# ESP8266.net
KiCad netlist of a schematic drawn in Altium Designer
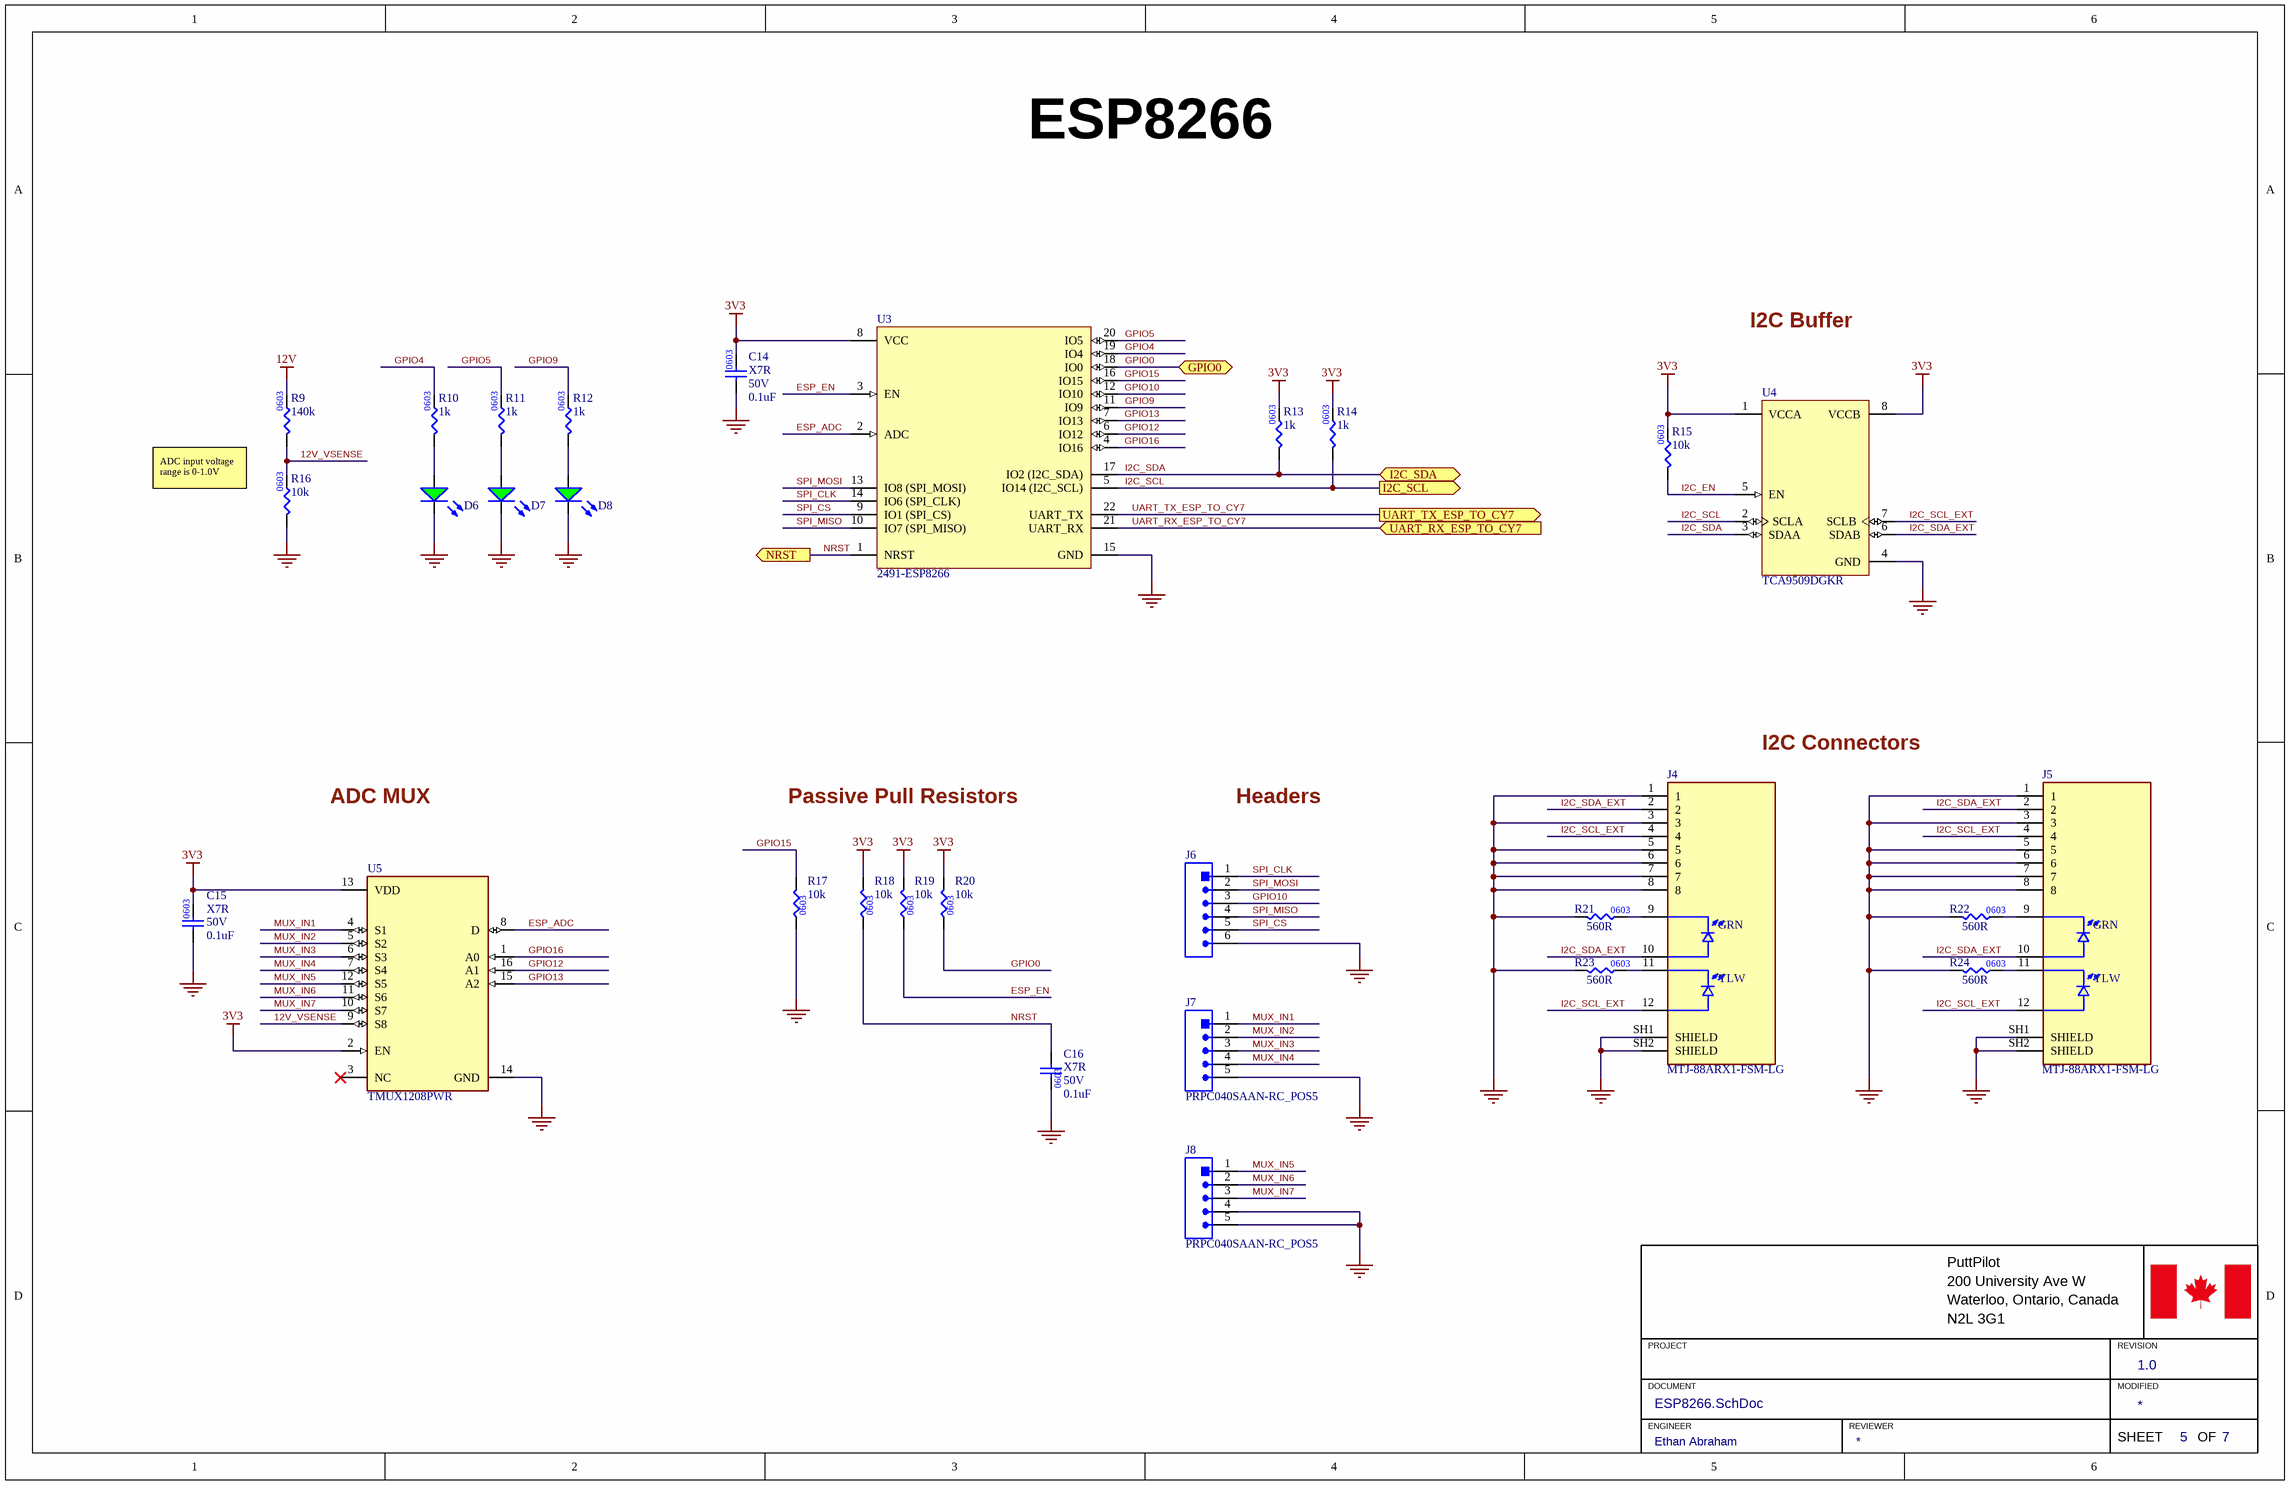
[diagram p0: ESP8266.SchDoc]

(export (version "E")
  (design (tool "Eeschema 10.0.6"))
  (components
    (comp (ref "C14")
      (value "GCJ188R71H104KA12D")
      (footprint ".CAP_0603")
      (description "CAP CER 0.1uF 50V X7R 0603")
      (fields
        (field (name "MANUFACTURER") "Murata")
        (field (name "TEMPERATURE CHARACTERISTICS CODE") "X7R")
        (field (name "RATED DC VOLTAGE (URDC)") "50V")
        (field (name "CAPACITANCE") "0.1uF")
      )
      (libsource (lib "PuttPilot") (part "GCJ188R71H104KA12D"))
    )
    (comp (ref "C15")
      (value "GCJ188R71H104KA12D")
      (footprint ".CAP_0603")
      (description "CAP CER 0.1uF 50V X7R 0603")
      (fields
        (field (name "MANUFACTURER") "Murata")
        (field (name "TEMPERATURE CHARACTERISTICS CODE") "X7R")
        (field (name "RATED DC VOLTAGE (URDC)") "50V")
        (field (name "CAPACITANCE") "0.1uF")
      )
      (libsource (lib "PuttPilot") (part "GCJ188R71H104KA12D"))
    )
    (comp (ref "C16")
      (value "GCJ188R71H104KA12D")
      (footprint ".CAP_0603")
      (description "CAP CER 0.1uF 50V X7R 0603")
      (fields
        (field (name "MANUFACTURER") "Murata")
        (field (name "TEMPERATURE CHARACTERISTICS CODE") "X7R")
        (field (name "RATED DC VOLTAGE (URDC)") "50V")
        (field (name "CAPACITANCE") "0.1uF")
      )
      (libsource (lib "PuttPilot") (part "GCJ188R71H104KA12D"))
    )
    (comp (ref "D6")
      (value "LTST-C191KGKT")
      (footprint ".LED_0603")
      (description "LED GREEN 2V 0603")
      (fields (field (name "MANUFACTURER") "Vishay Lite-On"))
      (libsource (lib "PuttPilot") (part "LTST-C191KGKT"))
    )
    (comp (ref "D7")
      (value "LTST-C191KGKT")
      (footprint ".LED_0603")
      (description "LED GREEN 2V 0603")
      (fields (field (name "MANUFACTURER") "Vishay Lite-On"))
      (libsource (lib "PuttPilot") (part "LTST-C191KGKT"))
    )
    (comp (ref "D8")
      (value "LTST-C191KGKT")
      (footprint ".LED_0603")
      (description "LED GREEN 2V 0603")
      (fields (field (name "MANUFACTURER") "Vishay Lite-On"))
      (libsource (lib "PuttPilot") (part "LTST-C191KGKT"))
    )
    (comp (ref "J4")
      (value "MTJ-88ARX1-FSM-LG")
      (footprint "MTJ-88ARX1-FSM-LG")
      (description "RJ45 JACK R/A SHIELDED")
      (fields (field (name "MANUFACTURER") "Adam Equipment"))
      (libsource (lib "PuttPilot") (part "MTJ-88ARX1-FSM-LG"))
    )
    (comp (ref "J5")
      (value "MTJ-88ARX1-FSM-LG")
      (footprint "MTJ-88ARX1-FSM-LG")
      (description "RJ45 JACK R/A SHIELDED")
      (fields (field (name "MANUFACTURER") "Adam Equipment"))
      (libsource (lib "PuttPilot") (part "MTJ-88ARX1-FSM-LG"))
    )
    (comp (ref "J6")
      (value "PRPC040SAAN-RC_POS6")
      (footprint "HEADER_6POS_2.54MM")
      (description "CONN HEADER VERT 6POS 2.54MM")
      (libsource (lib "PuttPilot") (part "PRPC040SAAN-RC_POS6"))
    )
    (comp (ref "J7")
      (value "PRPC040SAAN-RC_POS5")
      (footprint "HEADER_5POS_2.54MM")
      (description "CONN HEADER VERT 5POS 2.54MM")
      (libsource (lib "PuttPilot") (part "PRPC040SAAN-RC_POS5"))
    )
    (comp (ref "J8")
      (value "PRPC040SAAN-RC_POS5")
      (footprint "HEADER_5POS_2.54MM")
      (description "CONN HEADER VERT 5POS 2.54MM")
      (libsource (lib "PuttPilot") (part "PRPC040SAAN-RC_POS5"))
    )
    (comp (ref "R9")
      (value "RC0603FR-07140KL")
      (footprint ".RES_0603")
      (description "RES 140K OHM 0603")
      (fields
        (field (name "MANUFACTURER") "Yageo")
        (field (name "TOLERANCE") "1%")
        (field (name "RESISTANCE") "140k")
      )
      (libsource (lib "PuttPilot") (part "RC0603FR-07140KL"))
    )
    (comp (ref "R10")
      (value "RC0603FR-071KL")
      (footprint ".RES_0603")
      (description "RES 1K OHM 0603")
      (fields
        (field (name "MANUFACTURER") "Yageo")
        (field (name "TOLERANCE") "1%")
        (field (name "RESISTANCE") "1k")
      )
      (libsource (lib "PuttPilot") (part "RC0603FR-071KL"))
    )
    (comp (ref "R11")
      (value "RC0603FR-071KL")
      (footprint ".RES_0603")
      (description "RES 1K OHM 0603")
      (fields
        (field (name "MANUFACTURER") "Yageo")
        (field (name "TOLERANCE") "1%")
        (field (name "RESISTANCE") "1k")
      )
      (libsource (lib "PuttPilot") (part "RC0603FR-071KL"))
    )
    (comp (ref "R12")
      (value "RC0603FR-071KL")
      (footprint ".RES_0603")
      (description "RES 1K OHM 0603")
      (fields
        (field (name "MANUFACTURER") "Yageo")
        (field (name "TOLERANCE") "1%")
        (field (name "RESISTANCE") "1k")
      )
      (libsource (lib "PuttPilot") (part "RC0603FR-071KL"))
    )
    (comp (ref "R13")
      (value "RC0603FR-071KL")
      (footprint ".RES_0603")
      (description "RES 1K OHM 0603")
      (fields
        (field (name "MANUFACTURER") "Yageo")
        (field (name "TOLERANCE") "1%")
        (field (name "RESISTANCE") "1k")
      )
      (libsource (lib "PuttPilot") (part "RC0603FR-071KL"))
    )
    (comp (ref "R14")
      (value "RC0603FR-071KL")
      (footprint ".RES_0603")
      (description "RES 1K OHM 0603")
      (fields
        (field (name "MANUFACTURER") "Yageo")
        (field (name "TOLERANCE") "1%")
        (field (name "RESISTANCE") "1k")
      )
      (libsource (lib "PuttPilot") (part "RC0603FR-071KL"))
    )
    (comp (ref "R15")
      (value "RC0603FR-0710KL")
      (footprint ".RES_0603")
      (description "RES 10K OHM 0603")
      (fields
        (field (name "MANUFACTURER") "Yageo")
        (field (name "TOLERANCE") "1%")
        (field (name "RESISTANCE") "10k")
      )
      (libsource (lib "PuttPilot") (part "RC0603FR-0710KL"))
    )
    (comp (ref "R16")
      (value "RC0603FR-0710KL")
      (footprint ".RES_0603")
      (description "RES 10K OHM 0603")
      (fields
        (field (name "MANUFACTURER") "Yageo")
        (field (name "TOLERANCE") "1%")
        (field (name "RESISTANCE") "10k")
      )
      (libsource (lib "PuttPilot") (part "RC0603FR-0710KL"))
    )
    (comp (ref "R17")
      (value "RC0603FR-0710KL")
      (footprint ".RES_0603")
      (description "RES 10K OHM 0603")
      (fields
        (field (name "MANUFACTURER") "Yageo")
        (field (name "TOLERANCE") "1%")
        (field (name "RESISTANCE") "10k")
      )
      (libsource (lib "PuttPilot") (part "RC0603FR-0710KL"))
    )
    (comp (ref "R18")
      (value "RC0603FR-0710KL")
      (footprint ".RES_0603")
      (description "RES 10K OHM 0603")
      (fields
        (field (name "MANUFACTURER") "Yageo")
        (field (name "TOLERANCE") "1%")
        (field (name "RESISTANCE") "10k")
      )
      (libsource (lib "PuttPilot") (part "RC0603FR-0710KL"))
    )
    (comp (ref "R19")
      (value "RC0603FR-0710KL")
      (footprint ".RES_0603")
      (description "RES 10K OHM 0603")
      (fields
        (field (name "MANUFACTURER") "Yageo")
        (field (name "TOLERANCE") "1%")
        (field (name "RESISTANCE") "10k")
      )
      (libsource (lib "PuttPilot") (part "RC0603FR-0710KL"))
    )
    (comp (ref "R20")
      (value "RC0603FR-0710KL")
      (footprint ".RES_0603")
      (description "RES 10K OHM 0603")
      (fields
        (field (name "MANUFACTURER") "Yageo")
        (field (name "TOLERANCE") "1%")
        (field (name "RESISTANCE") "10k")
      )
      (libsource (lib "PuttPilot") (part "RC0603FR-0710KL"))
    )
    (comp (ref "R21")
      (value "RC0603FR-07560RL")
      (footprint ".RES_0603")
      (description "RES 560 OHM 0603")
      (fields
        (field (name "MANUFACTURER") "Yageo")
        (field (name "TOLERANCE") "1%")
        (field (name "RESISTANCE") "560R")
      )
      (libsource (lib "PuttPilot") (part "RC0603FR-07560RL"))
    )
    (comp (ref "R22")
      (value "RC0603FR-07560RL")
      (footprint ".RES_0603")
      (description "RES 560 OHM 0603")
      (fields
        (field (name "MANUFACTURER") "Yageo")
        (field (name "TOLERANCE") "1%")
        (field (name "RESISTANCE") "560R")
      )
      (libsource (lib "PuttPilot") (part "RC0603FR-07560RL"))
    )
    (comp (ref "R23")
      (value "RC0603FR-07560RL")
      (footprint ".RES_0603")
      (description "RES 560 OHM 0603")
      (fields
        (field (name "MANUFACTURER") "Yageo")
        (field (name "TOLERANCE") "1%")
        (field (name "RESISTANCE") "560R")
      )
      (libsource (lib "PuttPilot") (part "RC0603FR-07560RL"))
    )
    (comp (ref "R24")
      (value "RC0603FR-07560RL")
      (footprint ".RES_0603")
      (description "RES 560 OHM 0603")
      (fields
        (field (name "MANUFACTURER") "Yageo")
        (field (name "TOLERANCE") "1%")
        (field (name "RESISTANCE") "560R")
      )
      (libsource (lib "PuttPilot") (part "RC0603FR-07560RL"))
    )
    (comp (ref "U3")
      (value "2491-ESP8266")
      (footprint "2491-ESP8266")
      (description "ESP8266 + Trace Antenna, 4MB Flash")
      (libsource (lib "PuttPilot") (part "2491-ESP8266"))
    )
    (comp (ref "U4")
      (value "TCA9509DGKR")
      (footprint "TCA9509DGKR")
      (description "I2C BUFFER IC")
      (fields (field (name "MANUFACTURER") "Texas Instruments"))
      (libsource (lib "PuttPilot") (part "TCA9509DGKR"))
    )
    (comp (ref "U5")
      (value "TMUX1208PWR")
      (footprint "TMUX1208")
      (description "Single-Ended Multiplexer, 1 Func, 8 Channel, CMOS, PDSO16")
      (fields (field (name "MANUFACTURER") "Texas Instruments"))
      (libsource (lib "PuttPilot") (part "TMUX1208PWR"))
    )
  )
  (nets
    (net (code "1") (name "/12V_VSENSE") (class "Default")
      (node (ref "R16") (pin "2") (pinfunction "2_2") (pintype "passive"))
      (node (ref "R9") (pin "1") (pinfunction "1_1") (pintype "passive"))
      (node (ref "U5") (pin "9") (pinfunction "S8_9") (pintype "bidirectional"))
    )
    (net (code "2") (name "/ESP_ADC") (class "Default")
      (node (ref "U3") (pin "2") (pinfunction "ADC_2") (pintype "input"))
      (node (ref "U5") (pin "8") (pinfunction "D_8") (pintype "bidirectional"))
    )
    (net (code "3") (name "/ESP_EN") (class "Default")
      (node (ref "R19") (pin "1") (pinfunction "1_1") (pintype "passive"))
      (node (ref "U3") (pin "3") (pinfunction "EN_3") (pintype "input"))
    )
    (net (code "4") (name "/GPIO0") (class "Default")
      (node (ref "R20") (pin "1") (pinfunction "1_1") (pintype "passive"))
      (node (ref "U3") (pin "18") (pinfunction "IO0_18") (pintype "bidirectional"))
    )
    (net (code "5") (name "/GPIO4") (class "Default")
      (node (ref "R10") (pin "2") (pinfunction "2_2") (pintype "passive"))
      (node (ref "U3") (pin "19") (pinfunction "IO4_19") (pintype "bidirectional"))
    )
    (net (code "6") (name "/GPIO5") (class "Default")
      (node (ref "R11") (pin "2") (pinfunction "2_2") (pintype "passive"))
      (node (ref "U3") (pin "20") (pinfunction "IO5_20") (pintype "bidirectional"))
    )
    (net (code "7") (name "/GPIO9") (class "Default")
      (node (ref "R12") (pin "2") (pinfunction "2_2") (pintype "passive"))
      (node (ref "U3") (pin "11") (pinfunction "IO9_11") (pintype "bidirectional"))
    )
    (net (code "8") (name "/GPIO10") (class "Default")
      (node (ref "J6") (pin "3") (pinfunction "3_3") (pintype "passive"))
      (node (ref "U3") (pin "12") (pinfunction "IO10_12") (pintype "bidirectional"))
    )
    (net (code "9") (name "/GPIO12") (class "Default")
      (node (ref "U3") (pin "6") (pinfunction "IO12_6") (pintype "bidirectional"))
      (node (ref "U5") (pin "16") (pinfunction "A1_16") (pintype "input"))
    )
    (net (code "10") (name "/GPIO13") (class "Default")
      (node (ref "U3") (pin "7") (pinfunction "IO13_7") (pintype "bidirectional"))
      (node (ref "U5") (pin "15") (pinfunction "A2_15") (pintype "input"))
    )
    (net (code "11") (name "/GPIO15") (class "Default")
      (node (ref "R17") (pin "2") (pinfunction "2_2") (pintype "passive"))
      (node (ref "U3") (pin "16") (pinfunction "IO15_16") (pintype "bidirectional"))
    )
    (net (code "12") (name "/GPIO16") (class "Default")
      (node (ref "U3") (pin "4") (pinfunction "IO16_4") (pintype "bidirectional"))
      (node (ref "U5") (pin "1") (pinfunction "A0_1") (pintype "input"))
    )
    (net (code "13") (name "/I2C_EN") (class "Default")
      (node (ref "R15") (pin "1") (pinfunction "1_1") (pintype "passive"))
      (node (ref "U4") (pin "5") (pinfunction "EN_5") (pintype "input"))
    )
    (net (code "14") (name "/I2C_SCL") (class "Default")
      (node (ref "R14") (pin "1") (pinfunction "1_1") (pintype "passive"))
      (node (ref "U3") (pin "5") (pinfunction "IO14_(I2C_SCL)_5") (pintype "passive"))
      (node (ref "U4") (pin "2") (pinfunction "SCLA_2") (pintype "bidirectional"))
    )
    (net (code "15") (name "/I2C_SCL_EXT") (class "Default")
      (node (ref "J4") (pin "12") (pinfunction "12_12") (pintype "passive"))
      (node (ref "J4") (pin "4") (pinfunction "4_4") (pintype "passive"))
      (node (ref "J5") (pin "12") (pinfunction "12_12") (pintype "passive"))
      (node (ref "J5") (pin "4") (pinfunction "4_4") (pintype "passive"))
      (node (ref "U4") (pin "7") (pinfunction "SCLB_7") (pintype "bidirectional"))
    )
    (net (code "16") (name "/I2C_SDA") (class "Default")
      (node (ref "R13") (pin "1") (pinfunction "1_1") (pintype "passive"))
      (node (ref "U3") (pin "17") (pinfunction "IO2_(I2C_SDA)_17") (pintype "passive"))
      (node (ref "U4") (pin "3") (pinfunction "SDAA_3") (pintype "bidirectional"))
    )
    (net (code "17") (name "/I2C_SDA_EXT") (class "Default")
      (node (ref "J4") (pin "10") (pinfunction "10_10") (pintype "passive"))
      (node (ref "J4") (pin "2") (pinfunction "2_2") (pintype "passive"))
      (node (ref "J5") (pin "10") (pinfunction "10_10") (pintype "passive"))
      (node (ref "J5") (pin "2") (pinfunction "2_2") (pintype "passive"))
      (node (ref "U4") (pin "6") (pinfunction "SDAB_6") (pintype "bidirectional"))
    )
    (net (code "18") (name "/MUX_IN1") (class "Default")
      (node (ref "J7") (pin "1") (pinfunction "1_1") (pintype "passive"))
      (node (ref "U5") (pin "4") (pinfunction "S1_4") (pintype "bidirectional"))
    )
    (net (code "19") (name "/MUX_IN2") (class "Default")
      (node (ref "J7") (pin "2") (pinfunction "2_2") (pintype "passive"))
      (node (ref "U5") (pin "5") (pinfunction "S2_5") (pintype "bidirectional"))
    )
    (net (code "20") (name "/MUX_IN3") (class "Default")
      (node (ref "J7") (pin "3") (pinfunction "3_3") (pintype "passive"))
      (node (ref "U5") (pin "6") (pinfunction "S3_6") (pintype "bidirectional"))
    )
    (net (code "21") (name "/MUX_IN4") (class "Default")
      (node (ref "J7") (pin "4") (pinfunction "4_4") (pintype "passive"))
      (node (ref "U5") (pin "7") (pinfunction "S4_7") (pintype "bidirectional"))
    )
    (net (code "22") (name "/MUX_IN5") (class "Default")
      (node (ref "J8") (pin "1") (pinfunction "1_1") (pintype "passive"))
      (node (ref "U5") (pin "12") (pinfunction "S5_12") (pintype "bidirectional"))
    )
    (net (code "23") (name "/MUX_IN6") (class "Default")
      (node (ref "J8") (pin "2") (pinfunction "2_2") (pintype "passive"))
      (node (ref "U5") (pin "11") (pinfunction "S6_11") (pintype "bidirectional"))
    )
    (net (code "24") (name "/MUX_IN7") (class "Default")
      (node (ref "J8") (pin "3") (pinfunction "3_3") (pintype "passive"))
      (node (ref "U5") (pin "10") (pinfunction "S7_10") (pintype "bidirectional"))
    )
    (net (code "25") (name "/NRST") (class "Default")
      (node (ref "C16") (pin "2") (pinfunction "2_2") (pintype "passive"))
      (node (ref "R18") (pin "1") (pinfunction "1_1") (pintype "passive"))
      (node (ref "U3") (pin "1") (pinfunction "NRST_1") (pintype "passive"))
    )
    (net (code "26") (name "/SPI_CLK") (class "Default")
      (node (ref "J6") (pin "1") (pinfunction "1_1") (pintype "passive"))
      (node (ref "U3") (pin "14") (pinfunction "IO6_(SPI_CLK)_14") (pintype "passive"))
    )
    (net (code "27") (name "/SPI_CS") (class "Default")
      (node (ref "J6") (pin "5") (pinfunction "5_5") (pintype "passive"))
      (node (ref "U3") (pin "9") (pinfunction "IO1_(SPI_CS)_9") (pintype "passive"))
    )
    (net (code "28") (name "/SPI_MISO") (class "Default")
      (node (ref "J6") (pin "4") (pinfunction "4_4") (pintype "passive"))
      (node (ref "U3") (pin "10") (pinfunction "IO7_(SPI_MISO)_10") (pintype "passive"))
    )
    (net (code "29") (name "/SPI_MOSI") (class "Default")
      (node (ref "J6") (pin "2") (pinfunction "2_2") (pintype "passive"))
      (node (ref "U3") (pin "13") (pinfunction "IO8_(SPI_MOSI)_13") (pintype "passive"))
    )
    (net (code "30") (name "/UART_RX_ESP_TO_CY7") (class "Default")
      (node (ref "U3") (pin "21") (pinfunction "UART_RX_21") (pintype "passive"))
    )
    (net (code "31") (name "/UART_TX_ESP_TO_CY7") (class "Default")
      (node (ref "U3") (pin "22") (pinfunction "UART_TX_22") (pintype "passive"))
    )
    (net (code "32") (name "3V3") (class "Default")
      (node (ref "C14") (pin "2") (pinfunction "2_2") (pintype "passive"))
      (node (ref "C15") (pin "2") (pinfunction "2_2") (pintype "passive"))
      (node (ref "R13") (pin "2") (pinfunction "2_2") (pintype "passive"))
      (node (ref "R14") (pin "2") (pinfunction "2_2") (pintype "passive"))
      (node (ref "R15") (pin "2") (pinfunction "2_2") (pintype "passive"))
      (node (ref "R18") (pin "2") (pinfunction "2_2") (pintype "passive"))
      (node (ref "R19") (pin "2") (pinfunction "2_2") (pintype "passive"))
      (node (ref "R20") (pin "2") (pinfunction "2_2") (pintype "passive"))
      (node (ref "U3") (pin "8") (pinfunction "VCC_8") (pintype "power_in"))
      (node (ref "U4") (pin "1") (pinfunction "VCCA_1") (pintype "power_in"))
      (node (ref "U4") (pin "8") (pinfunction "VCCB_8") (pintype "power_in"))
      (node (ref "U5") (pin "13") (pinfunction "VDD_13") (pintype "power_in"))
      (node (ref "U5") (pin "2") (pinfunction "EN_2") (pintype "input"))
    )
    (net (code "33") (name "12V") (class "Default")
      (node (ref "R9") (pin "2") (pinfunction "2_2") (pintype "passive"))
    )
    (net (code "34") (name "GND") (class "Default")
      (node (ref "C14") (pin "1") (pinfunction "1_1") (pintype "passive"))
      (node (ref "C15") (pin "1") (pinfunction "1_1") (pintype "passive"))
      (node (ref "C16") (pin "1") (pinfunction "1_1") (pintype "passive"))
      (node (ref "D6") (pin "2") (pinfunction "K_2") (pintype "passive"))
      (node (ref "D7") (pin "2") (pinfunction "K_2") (pintype "passive"))
      (node (ref "D8") (pin "2") (pinfunction "K_2") (pintype "passive"))
      (node (ref "J4") (pin "1") (pinfunction "1_1") (pintype "passive"))
      (node (ref "J4") (pin "3") (pinfunction "3_3") (pintype "passive"))
      (node (ref "J4") (pin "5") (pinfunction "5_5") (pintype "passive"))
      (node (ref "J4") (pin "6") (pinfunction "6_6") (pintype "passive"))
      (node (ref "J4") (pin "7") (pinfunction "7_7") (pintype "passive"))
      (node (ref "J4") (pin "8") (pinfunction "8_8") (pintype "passive"))
      (node (ref "J4") (pin "SH1") (pinfunction "SHIELD_SH1") (pintype "passive"))
      (node (ref "J4") (pin "SH2") (pinfunction "SHIELD_SH2") (pintype "passive"))
      (node (ref "J5") (pin "1") (pinfunction "1_1") (pintype "passive"))
      (node (ref "J5") (pin "3") (pinfunction "3_3") (pintype "passive"))
      (node (ref "J5") (pin "5") (pinfunction "5_5") (pintype "passive"))
      (node (ref "J5") (pin "6") (pinfunction "6_6") (pintype "passive"))
      (node (ref "J5") (pin "7") (pinfunction "7_7") (pintype "passive"))
      (node (ref "J5") (pin "8") (pinfunction "8_8") (pintype "passive"))
      (node (ref "J5") (pin "SH1") (pinfunction "SHIELD_SH1") (pintype "passive"))
      (node (ref "J5") (pin "SH2") (pinfunction "SHIELD_SH2") (pintype "passive"))
      (node (ref "J6") (pin "6") (pinfunction "6_6") (pintype "passive"))
      (node (ref "J7") (pin "5") (pinfunction "5_5") (pintype "passive"))
      (node (ref "J8") (pin "4") (pinfunction "4_4") (pintype "passive"))
      (node (ref "J8") (pin "5") (pinfunction "5_5") (pintype "passive"))
      (node (ref "R16") (pin "1") (pinfunction "1_1") (pintype "passive"))
      (node (ref "R17") (pin "1") (pinfunction "1_1") (pintype "passive"))
      (node (ref "R21") (pin "1") (pinfunction "1_1") (pintype "passive"))
      (node (ref "R22") (pin "1") (pinfunction "1_1") (pintype "passive"))
      (node (ref "R23") (pin "1") (pinfunction "1_1") (pintype "passive"))
      (node (ref "R24") (pin "1") (pinfunction "1_1") (pintype "passive"))
      (node (ref "U3") (pin "15") (pinfunction "GND_15") (pintype "power_in"))
      (node (ref "U4") (pin "4") (pinfunction "GND_4") (pintype "power_in"))
      (node (ref "U5") (pin "14") (pinfunction "GND_14") (pintype "power_in"))
    )
    (net (code "35") (name "Net-(D6-A)") (class "Default")
      (node (ref "D6") (pin "1") (pinfunction "A_1") (pintype "passive"))
      (node (ref "R10") (pin "1") (pinfunction "1_1") (pintype "passive"))
    )
    (net (code "36") (name "Net-(D7-A)") (class "Default")
      (node (ref "D7") (pin "1") (pinfunction "A_1") (pintype "passive"))
      (node (ref "R11") (pin "1") (pinfunction "1_1") (pintype "passive"))
    )
    (net (code "37") (name "Net-(D8-A)") (class "Default")
      (node (ref "D8") (pin "1") (pinfunction "A_1") (pintype "passive"))
      (node (ref "R12") (pin "1") (pinfunction "1_1") (pintype "passive"))
    )
    (net (code "38") (name "Net-(J4-Pad9)") (class "Default")
      (node (ref "J4") (pin "9") (pinfunction "9_9") (pintype "passive"))
      (node (ref "R21") (pin "2") (pinfunction "2_2") (pintype "passive"))
    )
    (net (code "39") (name "Net-(J4-Pad11)") (class "Default")
      (node (ref "J4") (pin "11") (pinfunction "11_11") (pintype "passive"))
      (node (ref "R23") (pin "2") (pinfunction "2_2") (pintype "passive"))
    )
    (net (code "40") (name "Net-(J5-Pad9)") (class "Default")
      (node (ref "J5") (pin "9") (pinfunction "9_9") (pintype "passive"))
      (node (ref "R22") (pin "2") (pinfunction "2_2") (pintype "passive"))
    )
    (net (code "41") (name "Net-(J5-Pad11)") (class "Default")
      (node (ref "J5") (pin "11") (pinfunction "11_11") (pintype "passive"))
      (node (ref "R24") (pin "2") (pinfunction "2_2") (pintype "passive"))
    )
    (net (code "42") (name "unconnected-(U5-NC-Pad3)") (class "Default")
      (node (ref "U5") (pin "3") (pinfunction "NC_3") (pintype "passive+no_connect"))
    )
  )
)
